# ESP-WROOM02-Breakout_v10.net
KiCad netlist of a schematic drawn in EAGLE
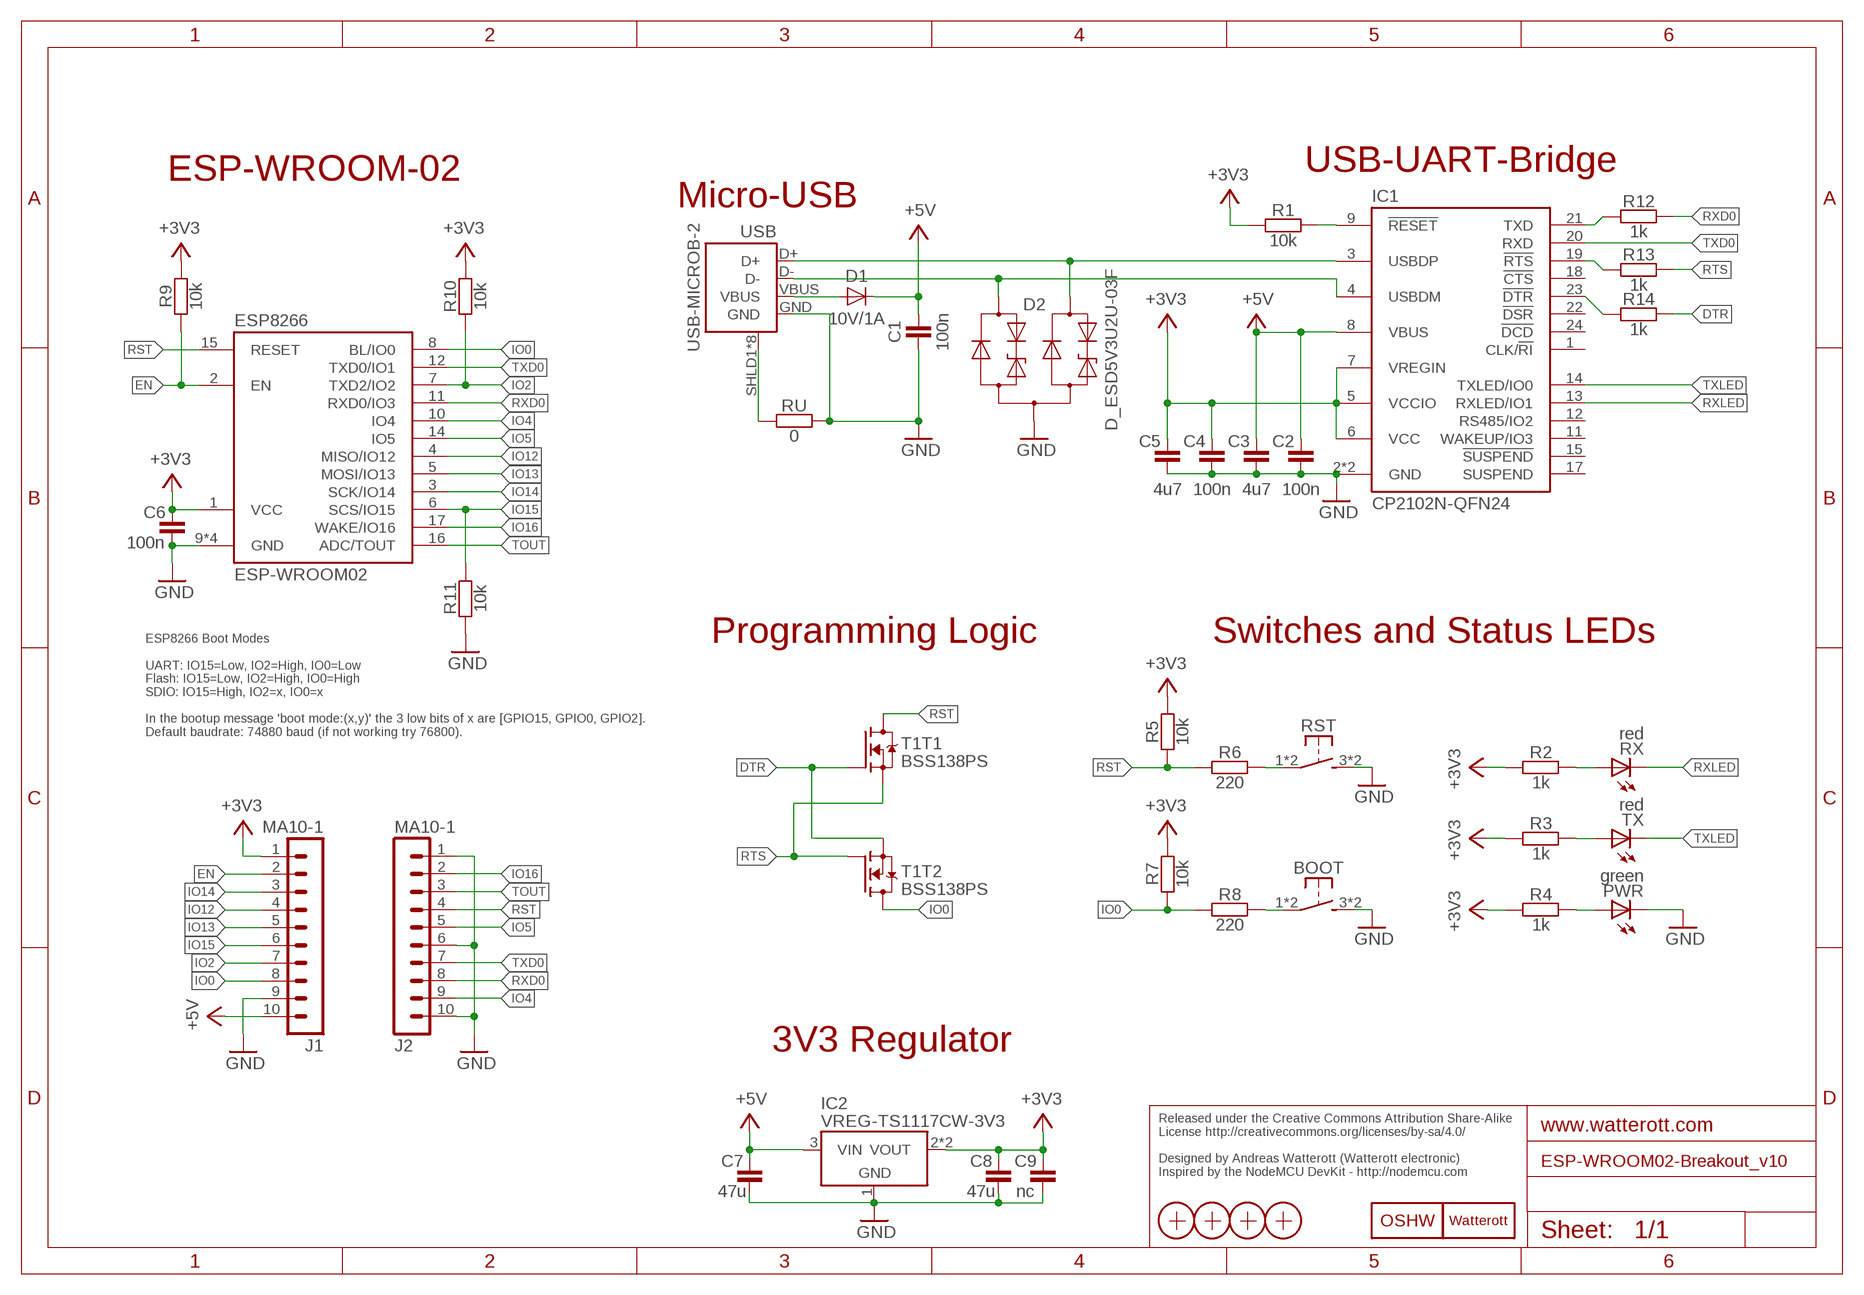
[diagram p0: schematic, sheet 1]

(export (version "E")
  (design (tool "Eeschema 10.0.6"))
  (components
    (comp (ref "BOOT")
      (value "SW-TACTILE-PTS840P")
      (footprint "eagle-import:PTS840P")
      (libsource (lib "eagle-import") (part "SW-TACTILE-PTS840P"))
    )
    (comp (ref "C1")
      (value "100n")
      (footprint "eagle-import:C0402")
      (libsource (lib "eagle-import") (part "CAPACITOR-0402"))
    )
    (comp (ref "C2")
      (value "100n")
      (footprint "eagle-import:C0402")
      (libsource (lib "eagle-import") (part "CAPACITOR-0402"))
    )
    (comp (ref "C3")
      (value "4u7")
      (footprint "eagle-import:C0603")
      (libsource (lib "eagle-import") (part "CAPACITOR-0603"))
    )
    (comp (ref "C4")
      (value "100n")
      (footprint "eagle-import:C0402")
      (libsource (lib "eagle-import") (part "CAPACITOR-0402"))
    )
    (comp (ref "C5")
      (value "4u7")
      (footprint "eagle-import:C0603")
      (libsource (lib "eagle-import") (part "CAPACITOR-0603"))
    )
    (comp (ref "C6")
      (value "100n")
      (footprint "eagle-import:C0402")
      (libsource (lib "eagle-import") (part "CAPACITOR-0402"))
    )
    (comp (ref "C7")
      (value "47u")
      (footprint "eagle-import:C1206")
      (libsource (lib "eagle-import") (part "CAPACITOR-1206"))
    )
    (comp (ref "C8")
      (value "47u")
      (footprint "eagle-import:C1206")
      (libsource (lib "eagle-import") (part "CAPACITOR-1206"))
    )
    (comp (ref "C9")
      (value "nc")
      (footprint "eagle-import:C1206")
      (libsource (lib "eagle-import") (part "CAPACITOR-1206"))
    )
    (comp (ref "D1")
      (value "10V/1A")
      (footprint "eagle-import:SMA_DO214AC")
      (libsource (lib "eagle-import") (part "DIODE-SMA"))
    )
    (comp (ref "D2")
      (value "D_ESD5V3U2U-03F")
      (footprint "eagle-import:SOT723")
      (libsource (lib "eagle-import") (part "D_ESD5V3U2U-03F"))
    )
    (comp (ref "ESP8266")
      (value "ESP-WROOM02")
      (footprint "eagle-import:ESP-WROOM02")
      (libsource (lib "eagle-import") (part "ESP-WROOM02"))
    )
    (comp (ref "IC1")
      (value "CP2102N-QFN24")
      (footprint "eagle-import:QFN24-PAD")
      (libsource (lib "eagle-import") (part "CP2102N-QFN24"))
    )
    (comp (ref "IC2")
      (value "VREG-TS1117CW-3V3")
      (footprint "eagle-import:SOT223")
      (libsource (lib "eagle-import") (part "VREG-TS1117CW-3V3"))
    )
    (comp (ref "J1")
      (value "MA10-1")
      (footprint "eagle-import:MA10-1")
      (libsource (lib "eagle-import") (part "MA10-1"))
    )
    (comp (ref "J2")
      (value "MA10-1")
      (footprint "eagle-import:MA10-1")
      (libsource (lib "eagle-import") (part "MA10-1"))
    )
    (comp (ref "LOGO2")
      (value "OSHW_LOGOX0070")
      (footprint "eagle-import:OSHW_6X70")
      (libsource (lib "eagle-import") (part "OSHW_LOGOX0070"))
    )
    (comp (ref "LOGO4")
      (value "LOGO-S_PLACE_M")
      (footprint "eagle-import:SPARK_TPLACE_M")
      (libsource (lib "eagle-import") (part "LOGO-S_PLACE_M"))
    )
    (comp (ref "PWR")
      (value "green")
      (footprint "eagle-import:C0603")
      (libsource (lib "eagle-import") (part "LED-0603"))
    )
    (comp (ref "R1")
      (value "10k")
      (footprint "eagle-import:C0402")
      (libsource (lib "eagle-import") (part "RESISTOR-0402"))
    )
    (comp (ref "R2")
      (value "1k")
      (footprint "eagle-import:C0402")
      (libsource (lib "eagle-import") (part "RESISTOR-0402"))
    )
    (comp (ref "R3")
      (value "1k")
      (footprint "eagle-import:C0402")
      (libsource (lib "eagle-import") (part "RESISTOR-0402"))
    )
    (comp (ref "R4")
      (value "1k")
      (footprint "eagle-import:C0402")
      (libsource (lib "eagle-import") (part "RESISTOR-0402"))
    )
    (comp (ref "R5")
      (value "10k")
      (footprint "eagle-import:C0402")
      (libsource (lib "eagle-import") (part "RESISTOR-0402"))
    )
    (comp (ref "R6")
      (value "220")
      (footprint "eagle-import:C0402")
      (libsource (lib "eagle-import") (part "RESISTOR-0402"))
    )
    (comp (ref "R7")
      (value "10k")
      (footprint "eagle-import:C0402")
      (libsource (lib "eagle-import") (part "RESISTOR-0402"))
    )
    (comp (ref "R8")
      (value "220")
      (footprint "eagle-import:C0402")
      (libsource (lib "eagle-import") (part "RESISTOR-0402"))
    )
    (comp (ref "R9")
      (value "10k")
      (footprint "eagle-import:C0402")
      (libsource (lib "eagle-import") (part "RESISTOR-0402"))
    )
    (comp (ref "R10")
      (value "10k")
      (footprint "eagle-import:C0402")
      (libsource (lib "eagle-import") (part "RESISTOR-0402"))
    )
    (comp (ref "R11")
      (value "10k")
      (footprint "eagle-import:C0402")
      (libsource (lib "eagle-import") (part "RESISTOR-0402"))
    )
    (comp (ref "R12")
      (value "1k")
      (footprint "eagle-import:C0402")
      (libsource (lib "eagle-import") (part "RESISTOR-0402"))
    )
    (comp (ref "R13")
      (value "1k")
      (footprint "eagle-import:C0402")
      (libsource (lib "eagle-import") (part "RESISTOR-0402"))
    )
    (comp (ref "R14")
      (value "1k")
      (footprint "eagle-import:C0402")
      (libsource (lib "eagle-import") (part "RESISTOR-0402"))
    )
    (comp (ref "RST")
      (value "SW-TACTILE-PTS840P")
      (footprint "eagle-import:PTS840P")
      (libsource (lib "eagle-import") (part "SW-TACTILE-PTS840P"))
    )
    (comp (ref "RU")
      (value "0")
      (footprint "eagle-import:C0402")
      (libsource (lib "eagle-import") (part "RESISTOR-0402"))
    )
    (comp (ref "RX")
      (value "red")
      (footprint "eagle-import:C0603")
      (libsource (lib "eagle-import") (part "LED-0603"))
    )
    (comp (ref "T1")
      (value "BSS138PS")
      (footprint "eagle-import:SOT363")
      (libsource (lib "eagle-import") (part "BSS138PS"))
    )
    (comp (ref "TX")
      (value "red")
      (footprint "eagle-import:C0603")
      (libsource (lib "eagle-import") (part "LED-0603"))
    )
    (comp (ref "USB")
      (value "USB-MICROB-2")
      (footprint "eagle-import:USB-MICROB-10118194")
      (libsource (lib "eagle-import") (part "USB-MICROB-2"))
    )
    (comp (ref "X1")
      (value "PASSER-07")
      (footprint "eagle-import:PASSER_07MM")
      (libsource (lib "eagle-import") (part "PASSER-07"))
    )
    (comp (ref "X2")
      (value "PASSER-07")
      (footprint "eagle-import:PASSER_07MM")
      (libsource (lib "eagle-import") (part "PASSER-07"))
    )
    (comp (ref "X3")
      (value "PASSER-07")
      (footprint "eagle-import:PASSER_07MM")
      (libsource (lib "eagle-import") (part "PASSER-07"))
    )
    (comp (ref "X4")
      (value "PASSER-07")
      (footprint "eagle-import:PASSER_07MM")
      (libsource (lib "eagle-import") (part "PASSER-07"))
    )
  )
  (nets
    (net (code "1") (name "+3V3") (class "Default")
      (node (ref "C4") (pin "2") (pinfunction "2_2") (pintype "passive"))
      (node (ref "C5") (pin "2") (pinfunction "2_2") (pintype "passive"))
      (node (ref "C6") (pin "2") (pinfunction "2_2") (pintype "passive"))
      (node (ref "C8") (pin "2") (pinfunction "2_2") (pintype "passive"))
      (node (ref "C9") (pin "2") (pinfunction "2_2") (pintype "passive"))
      (node (ref "ESP8266") (pin "1") (pinfunction "VCC_1") (pintype "power_in"))
      (node (ref "IC1") (pin "5") (pinfunction "VCCIO_5") (pintype "power_in"))
      (node (ref "IC1") (pin "6") (pinfunction "VCC_6") (pintype "power_in"))
      (node (ref "IC1") (pin "7") (pinfunction "VREGIN_7") (pintype "power_in"))
      (node (ref "IC2") (pin "2") (pinfunction "VOUT_2") (pintype "power_in"))
      (node (ref "IC2") (pin "4") (pinfunction "VOUT_4") (pintype "power_in"))
      (node (ref "J1") (pin "1") (pinfunction "1_1") (pintype "passive"))
      (node (ref "R1") (pin "1") (pinfunction "1_1") (pintype "passive"))
      (node (ref "R10") (pin "2") (pinfunction "2_2") (pintype "passive"))
      (node (ref "R2") (pin "1") (pinfunction "1_1") (pintype "passive"))
      (node (ref "R3") (pin "1") (pinfunction "1_1") (pintype "passive"))
      (node (ref "R4") (pin "1") (pinfunction "1_1") (pintype "passive"))
      (node (ref "R5") (pin "2") (pinfunction "2_2") (pintype "passive"))
      (node (ref "R7") (pin "2") (pinfunction "2_2") (pintype "passive"))
      (node (ref "R9") (pin "2") (pinfunction "2_2") (pintype "passive"))
    )
    (net (code "2") (name "+5V") (class "Default")
      (node (ref "C1") (pin "2") (pinfunction "2_2") (pintype "passive"))
      (node (ref "C2") (pin "2") (pinfunction "2_2") (pintype "passive"))
      (node (ref "C3") (pin "2") (pinfunction "2_2") (pintype "passive"))
      (node (ref "C7") (pin "2") (pinfunction "2_2") (pintype "passive"))
      (node (ref "D1") (pin "C") (pinfunction "C_C") (pintype "passive"))
      (node (ref "IC1") (pin "8") (pinfunction "VBUS_8") (pintype "power_in"))
      (node (ref "IC2") (pin "3") (pinfunction "VIN_3") (pintype "power_in"))
      (node (ref "J1") (pin "10") (pinfunction "10_10") (pintype "passive"))
    )
    (net (code "3") (name "DTR") (class "Default")
      (node (ref "R14") (pin "2") (pinfunction "2_2") (pintype "passive"))
      (node (ref "T1") (pin "2") (pinfunction "G_2") (pintype "passive"))
      (node (ref "T1") (pin "4") (pinfunction "S_4") (pintype "passive"))
    )
    (net (code "4") (name "EN") (class "Default")
      (node (ref "ESP8266") (pin "2") (pinfunction "EN_2") (pintype "bidirectional"))
      (node (ref "J1") (pin "2") (pinfunction "2_2") (pintype "passive"))
      (node (ref "R9") (pin "1") (pinfunction "1_1") (pintype "passive"))
    )
    (net (code "5") (name "GND") (class "Default")
      (node (ref "BOOT") (pin "3") (pinfunction "S1_3") (pintype "passive"))
      (node (ref "BOOT") (pin "4") (pinfunction "S1_4") (pintype "passive"))
      (node (ref "C1") (pin "1") (pinfunction "1_1") (pintype "passive"))
      (node (ref "C2") (pin "1") (pinfunction "1_1") (pintype "passive"))
      (node (ref "C3") (pin "1") (pinfunction "1_1") (pintype "passive"))
      (node (ref "C4") (pin "1") (pinfunction "1_1") (pintype "passive"))
      (node (ref "C5") (pin "1") (pinfunction "1_1") (pintype "passive"))
      (node (ref "C6") (pin "1") (pinfunction "1_1") (pintype "passive"))
      (node (ref "C7") (pin "1") (pinfunction "1_1") (pintype "passive"))
      (node (ref "C8") (pin "1") (pinfunction "1_1") (pintype "passive"))
      (node (ref "C9") (pin "1") (pinfunction "1_1") (pintype "passive"))
      (node (ref "D2") (pin "3") (pinfunction "A_3") (pintype "passive"))
      (node (ref "ESP8266") (pin "13") (pinfunction "GND_13") (pintype "power_in"))
      (node (ref "ESP8266") (pin "18") (pinfunction "GND_18") (pintype "power_in"))
      (node (ref "ESP8266") (pin "9") (pinfunction "GND_9") (pintype "power_in"))
      (node (ref "ESP8266") (pin "TP") (pinfunction "GND_TP") (pintype "power_in"))
      (node (ref "IC1") (pin "2") (pinfunction "GND_2") (pintype "power_in"))
      (node (ref "IC1") (pin "TP") (pinfunction "GND_TP") (pintype "power_in"))
      (node (ref "IC2") (pin "1") (pinfunction "GND_1") (pintype "power_in"))
      (node (ref "J1") (pin "9") (pinfunction "9_9") (pintype "passive"))
      (node (ref "J2") (pin "1") (pinfunction "1_1") (pintype "passive"))
      (node (ref "J2") (pin "10") (pinfunction "10_10") (pintype "passive"))
      (node (ref "J2") (pin "6") (pinfunction "6_6") (pintype "passive"))
      (node (ref "PWR") (pin "C") (pinfunction "C_C") (pintype "passive"))
      (node (ref "R11") (pin "1") (pinfunction "1_1") (pintype "passive"))
      (node (ref "RST") (pin "3") (pinfunction "S1_3") (pintype "passive"))
      (node (ref "RST") (pin "4") (pinfunction "S1_4") (pintype "passive"))
      (node (ref "RU") (pin "2") (pinfunction "2_2") (pintype "passive"))
      (node (ref "USB") (pin "GND") (pinfunction "GND_GND") (pintype "power_in"))
    )
    (net (code "6") (name "IO0") (class "Default")
      (node (ref "ESP8266") (pin "8") (pinfunction "BL/IO0_8") (pintype "bidirectional"))
      (node (ref "J1") (pin "8") (pinfunction "8_8") (pintype "passive"))
      (node (ref "R7") (pin "1") (pinfunction "1_1") (pintype "passive"))
      (node (ref "R8") (pin "1") (pinfunction "1_1") (pintype "passive"))
      (node (ref "T1") (pin "3") (pinfunction "D_3") (pintype "passive"))
    )
    (net (code "7") (name "IO2") (class "Default")
      (node (ref "ESP8266") (pin "7") (pinfunction "TXD2/IO2_7") (pintype "bidirectional"))
      (node (ref "J1") (pin "7") (pinfunction "7_7") (pintype "passive"))
      (node (ref "R10") (pin "1") (pinfunction "1_1") (pintype "passive"))
    )
    (net (code "8") (name "IO4") (class "Default")
      (node (ref "ESP8266") (pin "10") (pinfunction "IO4_10") (pintype "bidirectional"))
      (node (ref "J2") (pin "9") (pinfunction "9_9") (pintype "passive"))
    )
    (net (code "9") (name "IO5") (class "Default")
      (node (ref "ESP8266") (pin "14") (pinfunction "IO5_14") (pintype "bidirectional"))
      (node (ref "J2") (pin "5") (pinfunction "5_5") (pintype "passive"))
    )
    (net (code "10") (name "IO12") (class "Default")
      (node (ref "ESP8266") (pin "4") (pinfunction "MISO/IO12_4") (pintype "bidirectional"))
      (node (ref "J1") (pin "4") (pinfunction "4_4") (pintype "passive"))
    )
    (net (code "11") (name "IO13") (class "Default")
      (node (ref "ESP8266") (pin "5") (pinfunction "MOSI/IO13_5") (pintype "bidirectional"))
      (node (ref "J1") (pin "5") (pinfunction "5_5") (pintype "passive"))
    )
    (net (code "12") (name "IO14") (class "Default")
      (node (ref "ESP8266") (pin "3") (pinfunction "SCK/IO14_3") (pintype "bidirectional"))
      (node (ref "J1") (pin "3") (pinfunction "3_3") (pintype "passive"))
    )
    (net (code "13") (name "IO15") (class "Default")
      (node (ref "ESP8266") (pin "6") (pinfunction "SCS/IO15_6") (pintype "bidirectional"))
      (node (ref "J1") (pin "6") (pinfunction "6_6") (pintype "passive"))
      (node (ref "R11") (pin "2") (pinfunction "2_2") (pintype "passive"))
    )
    (net (code "14") (name "IO16") (class "Default")
      (node (ref "ESP8266") (pin "17") (pinfunction "WAKE/IO16_17") (pintype "bidirectional"))
      (node (ref "J2") (pin "2") (pinfunction "2_2") (pintype "passive"))
    )
    (net (code "15") (name "Net-(BOOT-P1-Pad1)") (class "Default")
      (node (ref "BOOT") (pin "1") (pinfunction "P1_1") (pintype "passive"))
      (node (ref "BOOT") (pin "2") (pinfunction "P1_2") (pintype "passive"))
      (node (ref "R8") (pin "2") (pinfunction "2_2") (pintype "passive"))
    )
    (net (code "16") (name "Net-(D1-PadA)") (class "Default")
      (node (ref "D1") (pin "A") (pinfunction "A_A") (pintype "passive"))
      (node (ref "USB") (pin "VBUS") (pinfunction "VBUS_VBUS") (pintype "power_in"))
    )
    (net (code "17") (name "Net-(D2-C1)") (class "Default")
      (node (ref "D2") (pin "1") (pinfunction "C1_1") (pintype "passive"))
      (node (ref "IC1") (pin "4") (pinfunction "USBDM_4") (pintype "bidirectional"))
      (node (ref "USB") (pin "D-") (pinfunction "D-_D-") (pintype "bidirectional"))
    )
    (net (code "18") (name "Net-(D2-C2)") (class "Default")
      (node (ref "D2") (pin "2") (pinfunction "C2_2") (pintype "passive"))
      (node (ref "IC1") (pin "3") (pinfunction "USBDP_3") (pintype "bidirectional"))
      (node (ref "USB") (pin "D+") (pinfunction "D+_D+") (pintype "bidirectional"))
    )
    (net (code "19") (name "Net-(IC1-TXD)") (class "Default")
      (node (ref "IC1") (pin "21") (pinfunction "TXD_21") (pintype "bidirectional"))
      (node (ref "R12") (pin "1") (pinfunction "1_1") (pintype "passive"))
    )
    (net (code "20") (name "Net-(IC1-~{DTR})") (class "Default")
      (node (ref "IC1") (pin "23") (pinfunction "~{DTR}_23") (pintype "bidirectional"))
      (node (ref "R14") (pin "1") (pinfunction "1_1") (pintype "passive"))
    )
    (net (code "21") (name "Net-(IC1-~{RESET})") (class "Default")
      (node (ref "IC1") (pin "9") (pinfunction "~{RESET}_9") (pintype "bidirectional"))
      (node (ref "R1") (pin "2") (pinfunction "2_2") (pintype "passive"))
    )
    (net (code "22") (name "Net-(IC1-~{RTS})") (class "Default")
      (node (ref "IC1") (pin "19") (pinfunction "~{RTS}_19") (pintype "bidirectional"))
      (node (ref "R13") (pin "1") (pinfunction "1_1") (pintype "passive"))
    )
    (net (code "23") (name "Net-(PWR-PadA)") (class "Default")
      (node (ref "PWR") (pin "A") (pinfunction "A_A") (pintype "passive"))
      (node (ref "R4") (pin "2") (pinfunction "2_2") (pintype "passive"))
    )
    (net (code "24") (name "Net-(R2-Pad2)") (class "Default")
      (node (ref "R2") (pin "2") (pinfunction "2_2") (pintype "passive"))
      (node (ref "RX") (pin "A") (pinfunction "A_A") (pintype "passive"))
    )
    (net (code "25") (name "Net-(R3-Pad2)") (class "Default")
      (node (ref "R3") (pin "2") (pinfunction "2_2") (pintype "passive"))
      (node (ref "TX") (pin "A") (pinfunction "A_A") (pintype "passive"))
    )
    (net (code "26") (name "Net-(R6-Pad2)") (class "Default")
      (node (ref "R6") (pin "2") (pinfunction "2_2") (pintype "passive"))
      (node (ref "RST") (pin "1") (pinfunction "P1_1") (pintype "passive"))
      (node (ref "RST") (pin "2") (pinfunction "P1_2") (pintype "passive"))
    )
    (net (code "27") (name "Net-(RU-Pad1)") (class "Default")
      (node (ref "RU") (pin "1") (pinfunction "1_1") (pintype "passive"))
      (node (ref "USB") (pin "SHLD1") (pinfunction "SHIELD_SHLD1") (pintype "passive"))
      (node (ref "USB") (pin "SHLD2") (pinfunction "SHIELD_SHLD2") (pintype "passive"))
      (node (ref "USB") (pin "SHLD3") (pinfunction "SHIELD_SHLD3") (pintype "passive"))
      (node (ref "USB") (pin "SHLD4") (pinfunction "SHIELD_SHLD4") (pintype "passive"))
      (node (ref "USB") (pin "SHLD5") (pinfunction "SHIELD_SHLD5") (pintype "passive"))
      (node (ref "USB") (pin "SHLD6") (pinfunction "SHIELD_SHLD6") (pintype "passive"))
      (node (ref "USB") (pin "SHLD7") (pinfunction "SHIELD_SHLD7") (pintype "passive"))
      (node (ref "USB") (pin "SHLD8") (pinfunction "SHIELD_SHLD8") (pintype "passive"))
    )
    (net (code "28") (name "RST") (class "Default")
      (node (ref "ESP8266") (pin "15") (pinfunction "RESET_15") (pintype "bidirectional"))
      (node (ref "J2") (pin "4") (pinfunction "4_4") (pintype "passive"))
      (node (ref "R5") (pin "1") (pinfunction "1_1") (pintype "passive"))
      (node (ref "R6") (pin "1") (pinfunction "1_1") (pintype "passive"))
      (node (ref "T1") (pin "6") (pinfunction "D_6") (pintype "passive"))
    )
    (net (code "29") (name "RTS") (class "Default")
      (node (ref "R13") (pin "2") (pinfunction "2_2") (pintype "passive"))
      (node (ref "T1") (pin "1") (pinfunction "S_1") (pintype "passive"))
      (node (ref "T1") (pin "5") (pinfunction "G_5") (pintype "passive"))
    )
    (net (code "30") (name "RXD0") (class "Default")
      (node (ref "ESP8266") (pin "11") (pinfunction "RXD0/IO3_11") (pintype "bidirectional"))
      (node (ref "J2") (pin "8") (pinfunction "8_8") (pintype "passive"))
      (node (ref "R12") (pin "2") (pinfunction "2_2") (pintype "passive"))
    )
    (net (code "31") (name "RXLED") (class "Default")
      (node (ref "IC1") (pin "13") (pinfunction "RXLED/IO1_13") (pintype "bidirectional"))
      (node (ref "RX") (pin "C") (pinfunction "C_C") (pintype "passive"))
    )
    (net (code "32") (name "TOUT") (class "Default")
      (node (ref "ESP8266") (pin "16") (pinfunction "ADC/TOUT_16") (pintype "bidirectional"))
      (node (ref "J2") (pin "3") (pinfunction "3_3") (pintype "passive"))
    )
    (net (code "33") (name "TXD0") (class "Default")
      (node (ref "ESP8266") (pin "12") (pinfunction "TXD0/IO1_12") (pintype "bidirectional"))
      (node (ref "IC1") (pin "20") (pinfunction "RXD_20") (pintype "bidirectional"))
      (node (ref "J2") (pin "7") (pinfunction "7_7") (pintype "passive"))
    )
    (net (code "34") (name "TXLED") (class "Default")
      (node (ref "IC1") (pin "14") (pinfunction "TXLED/IO0_14") (pintype "bidirectional"))
      (node (ref "TX") (pin "C") (pinfunction "C_C") (pintype "passive"))
    )
    (net (code "35") (name "unconnected-(IC1-CLK{slash}~{RI}-Pad1)") (class "Default")
      (node (ref "IC1") (pin "1") (pinfunction "CLK/~{RI}_1") (pintype "bidirectional"))
    )
    (net (code "36") (name "unconnected-(IC1-RS485{slash}IO2-Pad12)") (class "Default")
      (node (ref "IC1") (pin "12") (pinfunction "RS485/IO2_12") (pintype "bidirectional"))
    )
    (net (code "37") (name "unconnected-(IC1-SUSPEND-Pad17)") (class "Default")
      (node (ref "IC1") (pin "17") (pinfunction "SUSPEND_17") (pintype "bidirectional"))
    )
    (net (code "38") (name "unconnected-(IC1-WAKEUP{slash}IO3-Pad11)") (class "Default")
      (node (ref "IC1") (pin "11") (pinfunction "WAKEUP/IO3_11") (pintype "bidirectional"))
    )
    (net (code "39") (name "unconnected-(IC1-~{CTS}-Pad18)") (class "Default")
      (node (ref "IC1") (pin "18") (pinfunction "~{CTS}_18") (pintype "bidirectional"))
    )
    (net (code "40") (name "unconnected-(IC1-~{DCD}-Pad24)") (class "Default")
      (node (ref "IC1") (pin "24") (pinfunction "~{DCD}_24") (pintype "bidirectional"))
    )
    (net (code "41") (name "unconnected-(IC1-~{DSR}-Pad22)") (class "Default")
      (node (ref "IC1") (pin "22") (pinfunction "~{DSR}_22") (pintype "bidirectional"))
    )
    (net (code "42") (name "unconnected-(IC1-~{SUSPEND}-Pad15)") (class "Default")
      (node (ref "IC1") (pin "15") (pinfunction "~{SUSPEND}_15") (pintype "bidirectional"))
    )
  )
)
